# 3-RT5572-WLAN.net
KiCad netlist of a schematic drawn in Altium Designer
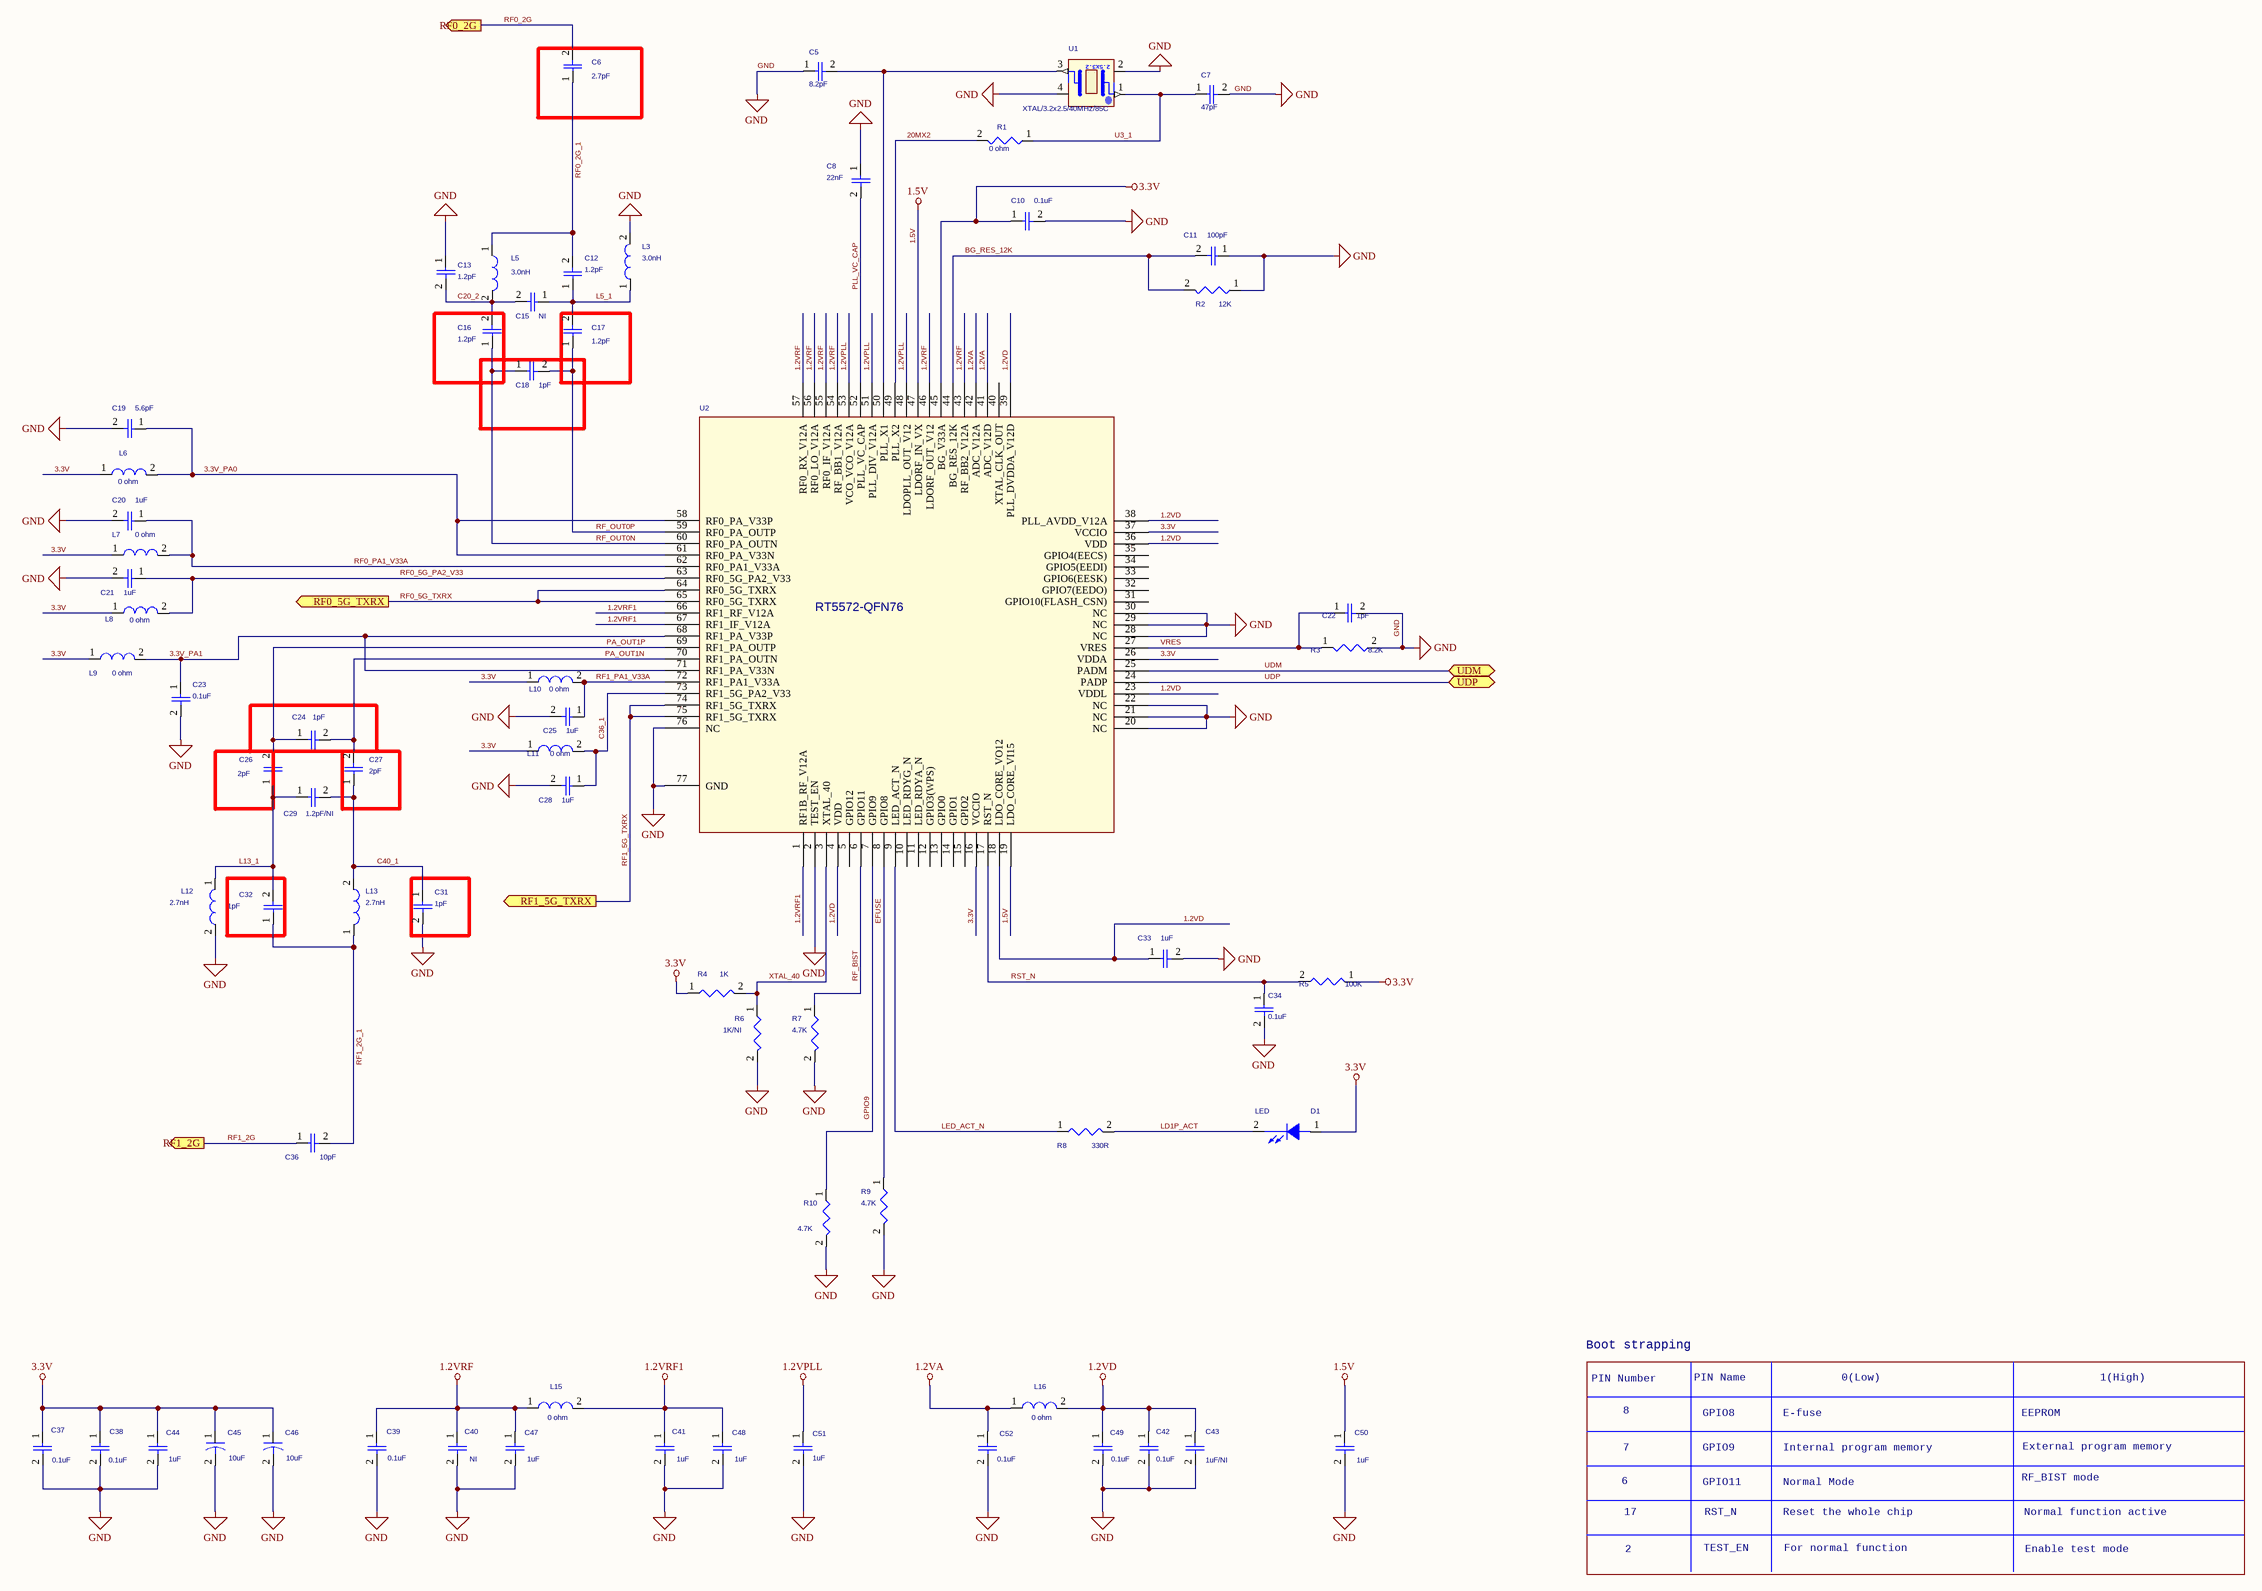
[diagram p0: 3-RT5572-WLAN.SchDoc]

(export (version "E")
  (design (tool "Eeschema 10.0.6"))
  (components
    (comp (ref "C5") (value "8.2pF") (footprint "0402") (libsource (lib "*") (part "CAP/0402")))
    (comp (ref "C6") (value "2.7pF") (footprint "0402") (libsource (lib "*") (part "CAP/0402")))
    (comp (ref "C7") (value "47pF") (footprint "0402") (libsource (lib "*") (part "CAP/0402")))
    (comp (ref "C8") (value "22nF") (footprint "0402") (libsource (lib "*") (part "CAP/0402")))
    (comp (ref "C10") (value "0.1uF") (footprint "0402") (libsource (lib "*") (part "CAP/0402")))
    (comp (ref "C11") (value "100pF") (footprint "0402") (libsource (lib "*") (part "CAP/0402")))
    (comp (ref "C12") (value "1.2pF") (footprint "0402") (libsource (lib "*") (part "CAP/0402")))
    (comp (ref "C13") (value "1.2pF") (footprint "0402") (libsource (lib "*") (part "CAP/0402")))
    (comp (ref "C15") (value "NI") (footprint "0402") (libsource (lib "*") (part "CAP/0402")))
    (comp (ref "C16") (value "1.2pF") (footprint "0402") (libsource (lib "*") (part "CAP/0402")))
    (comp (ref "C17") (value "1.2pF") (footprint "0402") (libsource (lib "*") (part "CAP/0402")))
    (comp (ref "C18") (value "1pF") (footprint "0402") (libsource (lib "*") (part "CAP/0402")))
    (comp (ref "C19") (value "5.6pF") (footprint "0402") (libsource (lib "*") (part "CAP/0402")))
    (comp (ref "C20") (value "1uF") (footprint "0402") (libsource (lib "*") (part "CAP/0402")))
    (comp (ref "C21") (value "1uF") (footprint "0402") (libsource (lib "*") (part "CAP/0402")))
    (comp (ref "C22") (value "1pF") (footprint "0402") (libsource (lib "*") (part "CAP/0402")))
    (comp (ref "C23") (value "0.1uF") (footprint "0402") (libsource (lib "*") (part "CAP/0402")))
    (comp (ref "C24") (value "1pF") (footprint "0402") (libsource (lib "*") (part "CAP/0402")))
    (comp (ref "C25") (value "1uF") (footprint "0402") (libsource (lib "*") (part "CAP/0402")))
    (comp (ref "C26") (value "2pF") (footprint "0402") (libsource (lib "*") (part "CAP/0402")))
    (comp (ref "C27") (value "2pF") (footprint "0402") (libsource (lib "*") (part "CAP/0402")))
    (comp (ref "C28") (value "1uF") (footprint "0402") (libsource (lib "*") (part "CAP/0402")))
    (comp (ref "C29") (value "1.2pF/NI") (footprint "0402") (libsource (lib "*") (part "CAP/0402")))
    (comp (ref "C31") (value "1pF") (footprint "0402") (libsource (lib "*") (part "CAP/0402")))
    (comp (ref "C32") (value "1pF") (footprint "0402") (libsource (lib "*") (part "CAP/0402")))
    (comp (ref "C33") (value "1uF") (footprint "0402") (libsource (lib "*") (part "CAP/0402")))
    (comp (ref "C34") (value "0.1uF") (footprint "0402") (libsource (lib "*") (part "CAP/0402")))
    (comp (ref "C36") (value "10pF") (footprint "0402") (libsource (lib "*") (part "CAP/0402")))
    (comp (ref "C37") (value "0.1uF") (footprint "0402") (libsource (lib "*") (part "CAP/0402")))
    (comp (ref "C38") (value "0.1uF") (footprint "0402") (libsource (lib "*") (part "CAP/0402")))
    (comp (ref "C39") (value "0.1uF") (footprint "0402") (libsource (lib "*") (part "CAP/0402")))
    (comp (ref "C40") (value "NI") (footprint "0402") (libsource (lib "*") (part "CAP/0402")))
    (comp (ref "C41") (value "1uF") (footprint "0402") (libsource (lib "*") (part "CAP/0402")))
    (comp (ref "C42") (value "0.1uF") (footprint "0402") (libsource (lib "*") (part "CAP/0402")))
    (comp (ref "C43") (value "1uF/NI") (footprint "0402") (libsource (lib "*") (part "CAP/0402")))
    (comp (ref "C44") (value "1uF") (footprint "0402") (libsource (lib "*") (part "CAP/0402")))
    (comp (ref "C45") (value "10uF") (libsource (lib "*") (part "CAP/0603")))
    (comp (ref "C46") (value "10uF") (libsource (lib "*") (part "CAP/0603")))
    (comp (ref "C47") (value "1uF") (footprint "0402") (libsource (lib "*") (part "CAP/0402")))
    (comp (ref "C48") (value "1uF") (footprint "0402") (libsource (lib "*") (part "CAP/0402")))
    (comp (ref "C49") (value "0.1uF") (footprint "0402") (libsource (lib "*") (part "CAP/0402")))
    (comp (ref "C50") (value "1uF") (footprint "0402") (libsource (lib "*") (part "CAP/0402")))
    (comp (ref "C51") (value "1uF") (footprint "0402") (libsource (lib "*") (part "CAP/0402")))
    (comp (ref "C52") (value "0.1uF") (footprint "0402") (libsource (lib "*") (part "CAP/0402")))
    (comp (ref "D1") (value "LED") (footprint "0603") (libsource (lib "*") (part "LED/0603")))
    (comp (ref "L3") (value "3.0nH") (footprint "0402") (libsource (lib "*") (part "L/0402")))
    (comp (ref "L5") (value "3.0nH") (footprint "0402") (libsource (lib "*") (part "L/0402")))
    (comp (ref "L6") (value "0 ohm") (footprint "0402") (libsource (lib "*") (part "L/0402")))
    (comp (ref "L7") (value "0 ohm") (footprint "0402") (libsource (lib "*") (part "L/0402")))
    (comp (ref "L8") (value "0 ohm") (footprint "0402") (libsource (lib "*") (part "L/0402")))
    (comp (ref "L9") (value "0 ohm") (footprint "0402") (libsource (lib "*") (part "L/0402")))
    (comp (ref "L10") (value "0 ohm") (footprint "0402") (libsource (lib "*") (part "L/0402")))
    (comp (ref "L11") (value "0 ohm") (footprint "0402") (libsource (lib "*") (part "L/0402")))
    (comp (ref "L12") (value "2.7nH") (footprint "0402") (libsource (lib "*") (part "L/0402_0")))
    (comp (ref "L13") (value "2.7nH") (footprint "0402") (libsource (lib "") (part "L/0402_1")))
    (comp (ref "L15") (value "0 ohm") (footprint "0402") (libsource (lib "*") (part "L/0402")))
    (comp (ref "L16") (value "0 ohm") (footprint "0402") (libsource (lib "*") (part "L/0402")))
    (comp (ref "R1") (value "0 ohm") (footprint "0402") (libsource (lib "*") (part "RES/0402_1_Dup1")))
    (comp (ref "R2") (value "12K") (footprint "0402") (libsource (lib "*") (part "RES/0402_1_Dup1")))
    (comp (ref "R3") (value "8.2K") (footprint "0402") (libsource (lib "*") (part "RES/0402_2")))
    (comp (ref "R4") (value "1K") (footprint "0402") (libsource (lib "*") (part "RES/0402_1_Dup2")))
    (comp (ref "R5") (value "100K") (footprint "0402") (libsource (lib "*") (part "RES/0402_1_Dup1")))
    (comp (ref "R6") (value "1K/NI") (footprint "0402") (libsource (lib "*") (part "RES/0402_1_Dup2")))
    (comp (ref "R7") (value "4.7K") (footprint "0402") (libsource (lib "*") (part "RES/0402_1_Dup2")))
    (comp (ref "R8") (value "330R") (footprint "0402") (libsource (lib "*") (part "RES/0402_1")))
    (comp (ref "R9") (value "4.7K") (footprint "0402") (libsource (lib "*") (part "RES/0402_1_Dup2")))
    (comp (ref "R10") (value "4.7K") (footprint "0402") (libsource (lib "*") (part "RES/0402_1_Dup2")))
    (comp (ref "U1")
      (value "XTAL/3.2x2.5/40MHz/85C")
      (footprint "XTAL-SMD/3.2X2.5")
      (libsource (lib "*") (part "XTAL_2.5"))
    )
    (comp (ref "U2") (value "RT5572-QFN76") (libsource (lib "*") (part "RT5572_5")))
  )
  (nets
    (net (code "1") (name "/3.3V_PA0") (class "Default")
      (node (ref "C19") (pin "1") (pinfunction "1_1") (pintype "passive"))
      (node (ref "L6") (pin "2") (pinfunction "2_2") (pintype "passive"))
      (node (ref "U2") (pin "58") (pinfunction "RF0_PA_V33P_58") (pintype "passive"))
      (node (ref "U2") (pin "61") (pinfunction "RF0_PA_V33N_61") (pintype "passive"))
    )
    (net (code "2") (name "/3.3V_PA1") (class "Default")
      (node (ref "C23") (pin "1") (pinfunction "1_1") (pintype "passive"))
      (node (ref "L9") (pin "2") (pinfunction "2_2") (pintype "passive"))
      (node (ref "U2") (pin "68") (pinfunction "RF1_PA_V33P_68") (pintype "passive"))
      (node (ref "U2") (pin "71") (pinfunction "RF1_PA_V33N_71") (pintype "passive"))
    )
    (net (code "3") (name "/20MX2") (class "Default")
      (node (ref "R1") (pin "2") (pinfunction "2_2") (pintype "passive"))
      (node (ref "U2") (pin "49") (pinfunction "PLL_X2_49") (pintype "passive"))
    )
    (net (code "4") (name "/BG_RES_12K") (class "Default")
      (node (ref "C11") (pin "2") (pinfunction "2_2") (pintype "passive"))
      (node (ref "R2") (pin "2") (pinfunction "2_2") (pintype "passive"))
      (node (ref "U2") (pin "44") (pinfunction "BG_RES_12K_44") (pintype "passive"))
    )
    (net (code "5") (name "/C20_2") (class "Default")
      (node (ref "C13") (pin "2") (pinfunction "2_2") (pintype "passive"))
      (node (ref "C15") (pin "2") (pinfunction "2_2") (pintype "passive"))
      (node (ref "C16") (pin "2") (pinfunction "2_2") (pintype "passive"))
      (node (ref "L5") (pin "2") (pinfunction "2_2") (pintype "passive"))
    )
    (net (code "6") (name "/C36_1") (class "Default")
      (node (ref "C28") (pin "1") (pinfunction "1_1") (pintype "passive"))
      (node (ref "L11") (pin "2") (pinfunction "2_2") (pintype "passive"))
      (node (ref "U2") (pin "73") (pinfunction "RF1_5G_PA2_V33_73") (pintype "passive"))
    )
    (net (code "7") (name "/C40_1") (class "Default")
      (node (ref "C27") (pin "1") (pinfunction "1_1") (pintype "passive"))
      (node (ref "C29") (pin "2") (pinfunction "2_2") (pintype "passive"))
      (node (ref "C31") (pin "1") (pinfunction "1_1") (pintype "passive"))
      (node (ref "L13") (pin "2") (pinfunction "2_2") (pintype "passive"))
    )
    (net (code "8") (name "/EFUSE") (class "Default")
      (node (ref "R9") (pin "1") (pinfunction "1_1") (pintype "passive"))
      (node (ref "U2") (pin "8") (pinfunction "GPIO8_8") (pintype "passive"))
    )
    (net (code "9") (name "/GPIO9") (class "Default")
      (node (ref "R10") (pin "1") (pinfunction "1_1") (pintype "passive"))
      (node (ref "U2") (pin "7") (pinfunction "GPIO9_7") (pintype "passive"))
    )
    (net (code "10") (name "/L5_1") (class "Default")
      (node (ref "C12") (pin "1") (pinfunction "1_1") (pintype "passive"))
      (node (ref "C15") (pin "1") (pinfunction "1_1") (pintype "passive"))
      (node (ref "C17") (pin "2") (pinfunction "2_2") (pintype "passive"))
      (node (ref "L3") (pin "1") (pinfunction "1_1") (pintype "passive"))
    )
    (net (code "11") (name "/L13_1") (class "Default")
      (node (ref "C26") (pin "1") (pinfunction "1_1") (pintype "passive"))
      (node (ref "C29") (pin "1") (pinfunction "1_1") (pintype "passive"))
      (node (ref "C32") (pin "2") (pinfunction "2_2") (pintype "passive"))
      (node (ref "L12") (pin "1") (pinfunction "1_1") (pintype "passive"))
    )
    (net (code "12") (name "/LD1P_ACT") (class "Default")
      (node (ref "D1") (pin "2") (pinfunction "CATHODE_2") (pintype "passive"))
      (node (ref "R8") (pin "2") (pinfunction "2_2") (pintype "passive"))
    )
    (net (code "13") (name "/LED_ACT_N") (class "Default")
      (node (ref "R8") (pin "1") (pinfunction "1_1") (pintype "passive"))
      (node (ref "U2") (pin "9") (pinfunction "LED_ACT_N_9") (pintype "passive"))
    )
    (net (code "14") (name "/PA_OUT1N") (class "Default")
      (node (ref "C24") (pin "2") (pinfunction "2_2") (pintype "passive"))
      (node (ref "C27") (pin "2") (pinfunction "2_2") (pintype "passive"))
      (node (ref "U2") (pin "70") (pinfunction "RF1_PA_OUTN_70") (pintype "passive"))
    )
    (net (code "15") (name "/PA_OUT1P") (class "Default")
      (node (ref "C24") (pin "1") (pinfunction "1_1") (pintype "passive"))
      (node (ref "C26") (pin "2") (pinfunction "2_2") (pintype "passive"))
      (node (ref "U2") (pin "69") (pinfunction "RF1_PA_OUTP_69") (pintype "passive"))
    )
    (net (code "16") (name "/PLL_VC_CAP") (class "Default")
      (node (ref "C8") (pin "2") (pinfunction "2_2") (pintype "passive"))
      (node (ref "U2") (pin "52") (pinfunction "PLL_VC_CAP_52") (pintype "passive"))
    )
    (net (code "17") (name "/RF0_2G") (class "Default")
      (node (ref "C6") (pin "2") (pinfunction "2_2") (pintype "passive"))
    )
    (net (code "18") (name "/RF0_2G_1") (class "Default")
      (node (ref "C12") (pin "2") (pinfunction "2_2") (pintype "passive"))
      (node (ref "C6") (pin "1") (pinfunction "1_1") (pintype "passive"))
      (node (ref "L5") (pin "1") (pinfunction "1_1") (pintype "passive"))
    )
    (net (code "19") (name "/RF0_5G_PA2_V33") (class "Default")
      (node (ref "C21") (pin "1") (pinfunction "1_1") (pintype "passive"))
      (node (ref "L8") (pin "2") (pinfunction "2_2") (pintype "passive"))
      (node (ref "U2") (pin "63") (pinfunction "RF0_5G_PA2_V33_63") (pintype "passive"))
    )
    (net (code "20") (name "/RF0_5G_TXRX") (class "Default")
      (node (ref "U2") (pin "64") (pinfunction "RF0_5G_TXRX_64") (pintype "passive"))
      (node (ref "U2") (pin "65") (pinfunction "RF0_5G_TXRX_65") (pintype "passive"))
    )
    (net (code "21") (name "/RF0_PA1_V33A") (class "Default")
      (node (ref "C20") (pin "1") (pinfunction "1_1") (pintype "passive"))
      (node (ref "L7") (pin "2") (pinfunction "2_2") (pintype "passive"))
      (node (ref "U2") (pin "62") (pinfunction "RF0_PA1_V33A_62") (pintype "passive"))
    )
    (net (code "22") (name "/RF1_2G") (class "Default")
      (node (ref "C36") (pin "1") (pinfunction "1_1") (pintype "passive"))
    )
    (net (code "23") (name "/RF1_2G_1") (class "Default")
      (node (ref "C32") (pin "1") (pinfunction "1_1") (pintype "passive"))
      (node (ref "C36") (pin "2") (pinfunction "2_2") (pintype "passive"))
      (node (ref "L13") (pin "1") (pinfunction "1_1") (pintype "passive"))
    )
    (net (code "24") (name "/RF1_5G_TXRX") (class "Default")
      (node (ref "U2") (pin "74") (pinfunction "RF1_5G_TXRX_74") (pintype "passive"))
      (node (ref "U2") (pin "75") (pinfunction "RF1_5G_TXRX_75") (pintype "passive"))
    )
    (net (code "25") (name "/RF1_PA1_V33A") (class "Default")
      (node (ref "C25") (pin "1") (pinfunction "1_1") (pintype "passive"))
      (node (ref "L10") (pin "2") (pinfunction "2_2") (pintype "passive"))
      (node (ref "U2") (pin "72") (pinfunction "RF1_PA1_V33A_72") (pintype "passive"))
    )
    (net (code "26") (name "/RF_BIST") (class "Default")
      (node (ref "R7") (pin "1") (pinfunction "1_1") (pintype "passive"))
      (node (ref "U2") (pin "6") (pinfunction "GPIO11_6") (pintype "passive"))
    )
    (net (code "27") (name "/RF_OUT0N") (class "Default")
      (node (ref "C16") (pin "1") (pinfunction "1_1") (pintype "passive"))
      (node (ref "C18") (pin "1") (pinfunction "1_1") (pintype "passive"))
      (node (ref "U2") (pin "60") (pinfunction "RF0_PA_OUTN_60") (pintype "passive"))
    )
    (net (code "28") (name "/RF_OUT0P") (class "Default")
      (node (ref "C17") (pin "1") (pinfunction "1_1") (pintype "passive"))
      (node (ref "C18") (pin "2") (pinfunction "2_2") (pintype "passive"))
      (node (ref "U2") (pin "59") (pinfunction "RF0_PA_OUTP_59") (pintype "passive"))
    )
    (net (code "29") (name "/RST_N") (class "Default")
      (node (ref "C34") (pin "1") (pinfunction "1_1") (pintype "passive"))
      (node (ref "R5") (pin "2") (pinfunction "2_2") (pintype "passive"))
      (node (ref "U2") (pin "17") (pinfunction "RST_N_17") (pintype "passive"))
    )
    (net (code "30") (name "/U3_1") (class "Default")
      (node (ref "C7") (pin "1") (pinfunction "1_1") (pintype "passive"))
      (node (ref "R1") (pin "1") (pinfunction "1_1") (pintype "passive"))
      (node (ref "U1") (pin "1") (pinfunction "X1_1") (pintype "output"))
    )
    (net (code "31") (name "/UDM") (class "Default")
      (node (ref "U2") (pin "25") (pinfunction "PADM_25") (pintype "passive"))
    )
    (net (code "32") (name "/UDP") (class "Default")
      (node (ref "U2") (pin "24") (pinfunction "PADP_24") (pintype "passive"))
    )
    (net (code "33") (name "/VRES") (class "Default")
      (node (ref "C22") (pin "1") (pinfunction "1_1") (pintype "passive"))
      (node (ref "R3") (pin "1") (pinfunction "1_1") (pintype "passive"))
      (node (ref "U2") (pin "27") (pinfunction "VRES_27") (pintype "passive"))
    )
    (net (code "34") (name "/XTAL_40") (class "Default")
      (node (ref "R4") (pin "2") (pinfunction "2_2") (pintype "passive"))
      (node (ref "R6") (pin "1") (pinfunction "1_1") (pintype "passive"))
      (node (ref "U2") (pin "3") (pinfunction "XTAL_40_3") (pintype "passive"))
    )
    (net (code "35") (name "1.2VA") (class "Default")
      (node (ref "C52") (pin "1") (pinfunction "1_1") (pintype "passive"))
      (node (ref "L16") (pin "1") (pinfunction "1_1") (pintype "passive"))
      (node (ref "U2") (pin "41") (pinfunction "ADC_V12D_41") (pintype "passive"))
      (node (ref "U2") (pin "42") (pinfunction "ADC_V12A_42") (pintype "passive"))
    )
    (net (code "36") (name "1.2VD") (class "Default")
      (node (ref "C33") (pin "1") (pinfunction "1_1") (pintype "passive"))
      (node (ref "C42") (pin "1") (pinfunction "1_1") (pintype "passive"))
      (node (ref "C43") (pin "1") (pinfunction "1_1") (pintype "passive"))
      (node (ref "C49") (pin "1") (pinfunction "1_1") (pintype "passive"))
      (node (ref "L16") (pin "2") (pinfunction "2_2") (pintype "passive"))
      (node (ref "U2") (pin "18") (pinfunction "LDO_CORE_VO12_18") (pintype "passive"))
      (node (ref "U2") (pin "23") (pinfunction "VDDL_23") (pintype "passive"))
      (node (ref "U2") (pin "36") (pinfunction "VDD_36") (pintype "passive"))
      (node (ref "U2") (pin "38") (pinfunction "PLL_AVDD_V12A_38") (pintype "passive"))
      (node (ref "U2") (pin "39") (pinfunction "PLL_DVDDA_V12D_39") (pintype "passive"))
      (node (ref "U2") (pin "4") (pinfunction "VDD_4") (pintype "passive"))
    )
    (net (code "37") (name "1.2VPLL") (class "Default")
      (node (ref "C51") (pin "1") (pinfunction "1_1") (pintype "passive"))
      (node (ref "U2") (pin "48") (pinfunction "LDOPLL_OUT_V12_48") (pintype "passive"))
      (node (ref "U2") (pin "51") (pinfunction "PLL_DIV_V12A_51") (pintype "passive"))
      (node (ref "U2") (pin "53") (pinfunction "VCO_VCO_V12A_53") (pintype "passive"))
    )
    (net (code "38") (name "1.2VRF") (class "Default")
      (node (ref "C39") (pin "1") (pinfunction "1_1") (pintype "passive"))
      (node (ref "C40") (pin "1") (pinfunction "1_1") (pintype "passive"))
      (node (ref "C47") (pin "1") (pinfunction "1_1") (pintype "passive"))
      (node (ref "L15") (pin "1") (pinfunction "1_1") (pintype "passive"))
      (node (ref "U2") (pin "43") (pinfunction "RF_BB2_V12A_43") (pintype "passive"))
      (node (ref "U2") (pin "46") (pinfunction "LDORF_OUT_V12_46") (pintype "passive"))
      (node (ref "U2") (pin "54") (pinfunction "RF_BB1_V12A_54") (pintype "passive"))
      (node (ref "U2") (pin "55") (pinfunction "RF0_IF_V12A_55") (pintype "passive"))
      (node (ref "U2") (pin "56") (pinfunction "RF0_LO_V12A_56") (pintype "passive"))
      (node (ref "U2") (pin "57") (pinfunction "RF0_RX_V12A_57") (pintype "passive"))
    )
    (net (code "39") (name "1.2VRF1") (class "Default")
      (node (ref "C41") (pin "1") (pinfunction "1_1") (pintype "passive"))
      (node (ref "C48") (pin "1") (pinfunction "1_1") (pintype "passive"))
      (node (ref "L15") (pin "2") (pinfunction "2_2") (pintype "passive"))
      (node (ref "U2") (pin "1") (pinfunction "RF1B_RF_V12A_1") (pintype "passive"))
      (node (ref "U2") (pin "66") (pinfunction "RF1_RF_V12A_66") (pintype "passive"))
      (node (ref "U2") (pin "67") (pinfunction "RF1_IF_V12A_67") (pintype "passive"))
    )
    (net (code "40") (name "1.5V") (class "Default")
      (node (ref "C50") (pin "1") (pinfunction "1_1") (pintype "passive"))
      (node (ref "U2") (pin "19") (pinfunction "LDO_CORE_VI15_19") (pintype "passive"))
      (node (ref "U2") (pin "47") (pinfunction "LDORF_IN_VX_47") (pintype "passive"))
    )
    (net (code "41") (name "3.3V") (class "Default")
      (node (ref "C10") (pin "1") (pinfunction "1_1") (pintype "passive"))
      (node (ref "C37") (pin "1") (pinfunction "1_1") (pintype "passive"))
      (node (ref "C38") (pin "1") (pinfunction "1_1") (pintype "passive"))
      (node (ref "C44") (pin "1") (pinfunction "1_1") (pintype "passive"))
      (node (ref "C45") (pin "1") (pinfunction "1_1") (pintype "passive"))
      (node (ref "C46") (pin "1") (pinfunction "1_1") (pintype "passive"))
      (node (ref "D1") (pin "1") (pinfunction "ANODE_1") (pintype "passive"))
      (node (ref "L10") (pin "1") (pinfunction "1_1") (pintype "passive"))
      (node (ref "L11") (pin "1") (pinfunction "1_1") (pintype "passive"))
      (node (ref "L6") (pin "1") (pinfunction "1_1") (pintype "passive"))
      (node (ref "L7") (pin "1") (pinfunction "1_1") (pintype "passive"))
      (node (ref "L8") (pin "1") (pinfunction "1_1") (pintype "passive"))
      (node (ref "L9") (pin "1") (pinfunction "1_1") (pintype "passive"))
      (node (ref "R4") (pin "1") (pinfunction "1_1") (pintype "passive"))
      (node (ref "R5") (pin "1") (pinfunction "1_1") (pintype "passive"))
      (node (ref "U2") (pin "16") (pinfunction "VCCIO_16") (pintype "passive"))
      (node (ref "U2") (pin "26") (pinfunction "VDDA_26") (pintype "passive"))
      (node (ref "U2") (pin "37") (pinfunction "VCCIO_37") (pintype "passive"))
      (node (ref "U2") (pin "45") (pinfunction "BG_V33A_45") (pintype "passive"))
    )
    (net (code "42") (name "GND") (class "Default")
      (node (ref "C10") (pin "2") (pinfunction "2_2") (pintype "passive"))
      (node (ref "C11") (pin "1") (pinfunction "1_1") (pintype "passive"))
      (node (ref "C13") (pin "1") (pinfunction "1_1") (pintype "passive"))
      (node (ref "C19") (pin "2") (pinfunction "2_2") (pintype "passive"))
      (node (ref "C20") (pin "2") (pinfunction "2_2") (pintype "passive"))
      (node (ref "C21") (pin "2") (pinfunction "2_2") (pintype "passive"))
      (node (ref "C22") (pin "2") (pinfunction "2_2") (pintype "passive"))
      (node (ref "C23") (pin "2") (pinfunction "2_2") (pintype "passive"))
      (node (ref "C25") (pin "2") (pinfunction "2_2") (pintype "passive"))
      (node (ref "C28") (pin "2") (pinfunction "2_2") (pintype "passive"))
      (node (ref "C31") (pin "2") (pinfunction "2_2") (pintype "passive"))
      (node (ref "C33") (pin "2") (pinfunction "2_2") (pintype "passive"))
      (node (ref "C34") (pin "2") (pinfunction "2_2") (pintype "passive"))
      (node (ref "C37") (pin "2") (pinfunction "2_2") (pintype "passive"))
      (node (ref "C38") (pin "2") (pinfunction "2_2") (pintype "passive"))
      (node (ref "C39") (pin "2") (pinfunction "2_2") (pintype "passive"))
      (node (ref "C40") (pin "2") (pinfunction "2_2") (pintype "passive"))
      (node (ref "C41") (pin "2") (pinfunction "2_2") (pintype "passive"))
      (node (ref "C42") (pin "2") (pinfunction "2_2") (pintype "passive"))
      (node (ref "C43") (pin "2") (pinfunction "2_2") (pintype "passive"))
      (node (ref "C44") (pin "2") (pinfunction "2_2") (pintype "passive"))
      (node (ref "C45") (pin "2") (pinfunction "2_2") (pintype "passive"))
      (node (ref "C46") (pin "2") (pinfunction "2_2") (pintype "passive"))
      (node (ref "C47") (pin "2") (pinfunction "2_2") (pintype "passive"))
      (node (ref "C48") (pin "2") (pinfunction "2_2") (pintype "passive"))
      (node (ref "C49") (pin "2") (pinfunction "2_2") (pintype "passive"))
      (node (ref "C5") (pin "1") (pinfunction "1_1") (pintype "passive"))
      (node (ref "C50") (pin "2") (pinfunction "2_2") (pintype "passive"))
      (node (ref "C51") (pin "2") (pinfunction "2_2") (pintype "passive"))
      (node (ref "C52") (pin "2") (pinfunction "2_2") (pintype "passive"))
      (node (ref "C7") (pin "2") (pinfunction "2_2") (pintype "passive"))
      (node (ref "C8") (pin "1") (pinfunction "1_1") (pintype "passive"))
      (node (ref "L12") (pin "2") (pinfunction "2_2") (pintype "passive"))
      (node (ref "L3") (pin "2") (pinfunction "2_2") (pintype "passive"))
      (node (ref "R10") (pin "2") (pinfunction "2_2") (pintype "passive"))
      (node (ref "R2") (pin "1") (pinfunction "1_1") (pintype "passive"))
      (node (ref "R3") (pin "2") (pinfunction "2_2") (pintype "passive"))
      (node (ref "R6") (pin "2") (pinfunction "2_2") (pintype "passive"))
      (node (ref "R7") (pin "2") (pinfunction "2_2") (pintype "passive"))
      (node (ref "R9") (pin "2") (pinfunction "2_2") (pintype "passive"))
      (node (ref "U1") (pin "2") (pinfunction "NC_2") (pintype "passive"))
      (node (ref "U1") (pin "4") (pinfunction "NC_4") (pintype "passive"))
      (node (ref "U2") (pin "2") (pinfunction "TEST_EN_2") (pintype "passive"))
      (node (ref "U2") (pin "20") (pinfunction "NC_20") (pintype "passive"))
      (node (ref "U2") (pin "21") (pinfunction "NC_21") (pintype "passive"))
      (node (ref "U2") (pin "22") (pinfunction "NC_22") (pintype "passive"))
      (node (ref "U2") (pin "28") (pinfunction "NC_28") (pintype "passive"))
      (node (ref "U2") (pin "29") (pinfunction "NC_29") (pintype "passive"))
      (node (ref "U2") (pin "30") (pinfunction "NC_30") (pintype "passive"))
      (node (ref "U2") (pin "76") (pinfunction "NC_76") (pintype "passive"))
      (node (ref "U2") (pin "77") (pinfunction "GND_77") (pintype "passive"))
    )
    (net (code "43") (name "Net-(U1-X2)") (class "Default")
      (node (ref "C5") (pin "2") (pinfunction "2_2") (pintype "passive"))
      (node (ref "U1") (pin "3") (pinfunction "X2_3") (pintype "output"))
      (node (ref "U2") (pin "50") (pinfunction "PLL_X1_50") (pintype "passive"))
    )
    (net (code "44") (name "unconnected-(U2-GPIO0-Pad13)") (class "Default")
      (node (ref "U2") (pin "13") (pinfunction "GPIO0_13") (pintype "passive"))
    )
    (net (code "45") (name "unconnected-(U2-GPIO1-Pad14)") (class "Default")
      (node (ref "U2") (pin "14") (pinfunction "GPIO1_14") (pintype "passive"))
    )
    (net (code "46") (name "unconnected-(U2-GPIO2-Pad15)") (class "Default")
      (node (ref "U2") (pin "15") (pinfunction "GPIO2_15") (pintype "passive"))
    )
    (net (code "47") (name "unconnected-(U2-GPIO3(WPS)-Pad12)") (class "Default")
      (node (ref "U2") (pin "12") (pinfunction "GPIO3(WPS)_12") (pintype "passive"))
    )
    (net (code "48") (name "unconnected-(U2-GPIO4(EECS)-Pad35)") (class "Default")
      (node (ref "U2") (pin "35") (pinfunction "GPIO4(EECS)_35") (pintype "passive"))
    )
    (net (code "49") (name "unconnected-(U2-GPIO5(EEDI)-Pad34)") (class "Default")
      (node (ref "U2") (pin "34") (pinfunction "GPIO5(EEDI)_34") (pintype "passive"))
    )
    (net (code "50") (name "unconnected-(U2-GPIO6(EESK)-Pad33)") (class "Default")
      (node (ref "U2") (pin "33") (pinfunction "GPIO6(EESK)_33") (pintype "passive"))
    )
    (net (code "51") (name "unconnected-(U2-GPIO7(EEDO)-Pad32)") (class "Default")
      (node (ref "U2") (pin "32") (pinfunction "GPIO7(EEDO)_32") (pintype "passive"))
    )
    (net (code "52") (name "unconnected-(U2-GPIO10(FLASH_CSN)-Pad31)") (class "Default")
      (node (ref "U2") (pin "31") (pinfunction "GPIO10(FLASH_CSN)_31") (pintype "passive"))
    )
    (net (code "53") (name "unconnected-(U2-GPIO12-Pad5)") (class "Default")
      (node (ref "U2") (pin "5") (pinfunction "GPIO12_5") (pintype "passive"))
    )
    (net (code "54") (name "unconnected-(U2-LED_RDYA_N-Pad11)") (class "Default")
      (node (ref "U2") (pin "11") (pinfunction "LED_RDYA_N_11") (pintype "passive"))
    )
    (net (code "55") (name "unconnected-(U2-LED_RDYG_N-Pad10)") (class "Default")
      (node (ref "U2") (pin "10") (pinfunction "LED_RDYG_N_10") (pintype "passive"))
    )
    (net (code "56") (name "unconnected-(U2-XTAL_CLK_OUT-Pad40)") (class "Default")
      (node (ref "U2") (pin "40") (pinfunction "XTAL_CLK_OUT_40") (pintype "passive"))
    )
  )
)
